# 02_MCU.net
KiCad netlist of a schematic drawn in Altium Designer
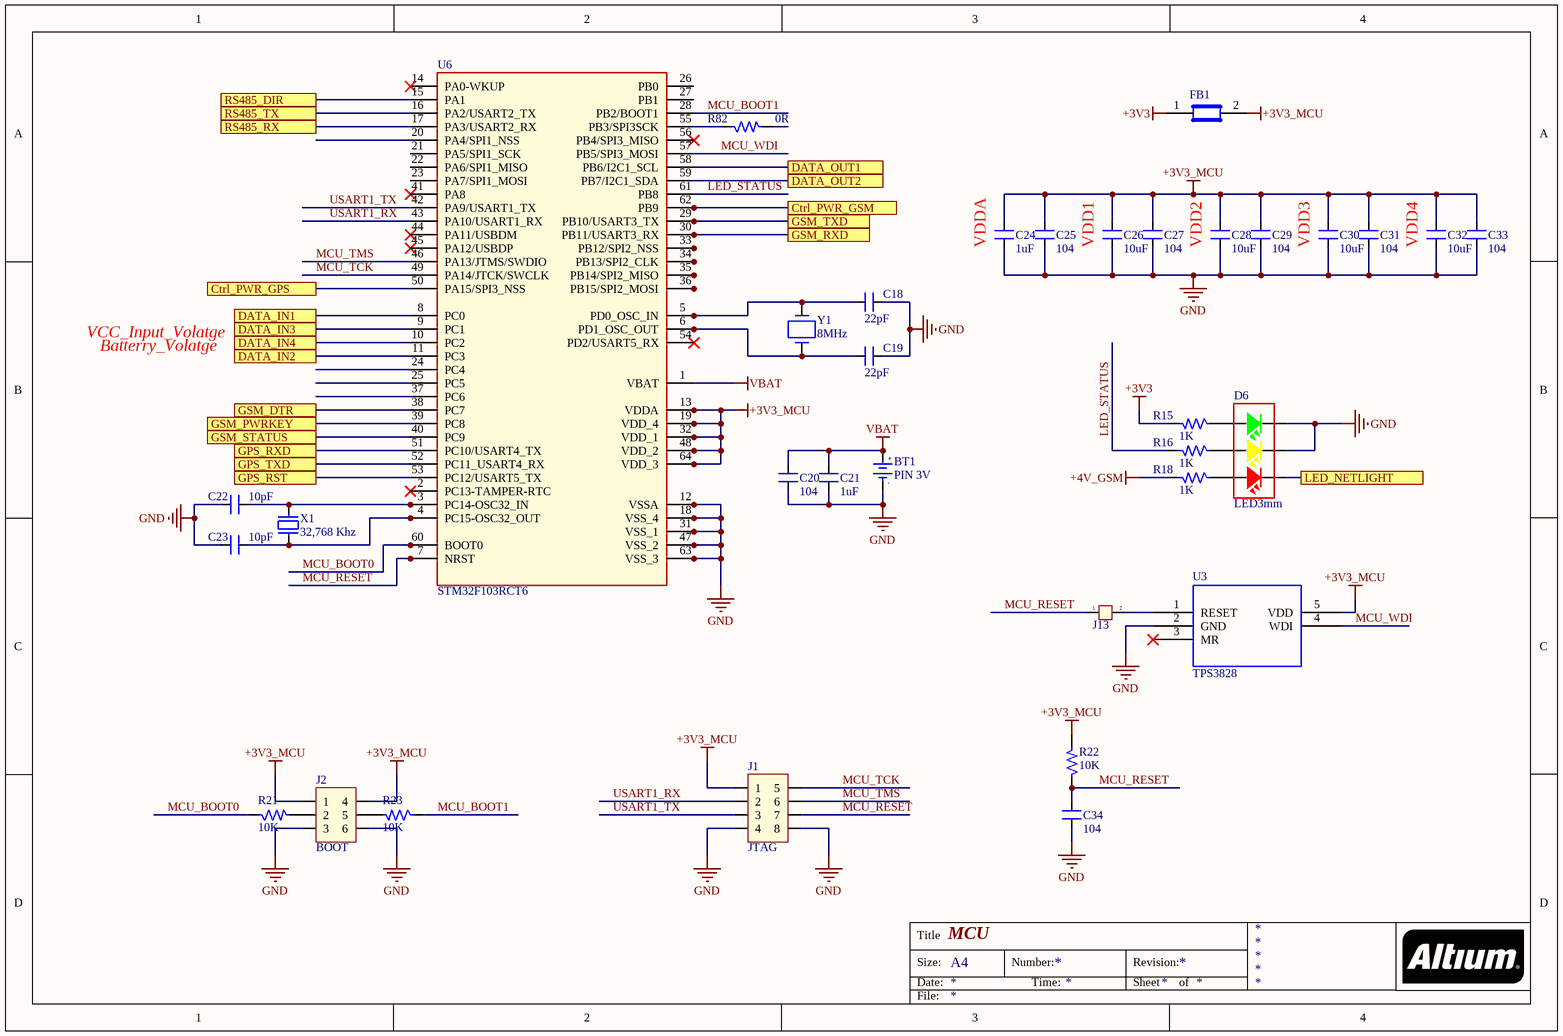
[diagram p0: [02] MCU.SchDoc]

(export (version "E")
  (design (tool "Eeschema 10.0.6"))
  (components
    (comp (ref "BT1")
      (value "PIN 3V")
      (footprint "PIN3V_mini")
      (description "Battery 3VDC")
      (libsource (lib "khapham") (part "PIN 3V"))
    )
    (comp (ref "C18")
      (value "22pF")
      (footprint "C0603 SMT")
      (description "Cap SMD")
      (libsource (lib "khapham") (part "CM"))
    )
    (comp (ref "C19")
      (value "22pF")
      (footprint "C0603 SMT")
      (description "Cap SMD")
      (libsource (lib "khapham") (part "CM"))
    )
    (comp (ref "C20")
      (value "104")
      (footprint "C0603 SMT")
      (description "Cap SMD")
      (libsource (lib "khapham") (part "CM"))
    )
    (comp (ref "C21")
      (value "1uF")
      (footprint "C0603 SMT")
      (description "Cap SMD")
      (libsource (lib "khapham") (part "CM"))
    )
    (comp (ref "C22")
      (value "10pF")
      (footprint "C0603 SMT")
      (description "Cap SMD")
      (libsource (lib "khapham") (part "CM"))
    )
    (comp (ref "C23")
      (value "10pF")
      (footprint "C0603 SMT")
      (description "Cap SMD")
      (libsource (lib "khapham") (part "CM"))
    )
    (comp (ref "C24")
      (value "1uF")
      (footprint "C0603 SMT")
      (description "Cap SMD")
      (libsource (lib "khapham") (part "CM"))
    )
    (comp (ref "C25")
      (value "104")
      (footprint "C0603 SMT")
      (description "Cap SMD")
      (libsource (lib "khapham") (part "CM"))
    )
    (comp (ref "C26")
      (value "10uF")
      (footprint "C0603 SMT")
      (description "Cap SMD")
      (libsource (lib "khapham") (part "CM"))
    )
    (comp (ref "C27")
      (value "104")
      (footprint "C0603 SMT")
      (description "Cap SMD")
      (libsource (lib "khapham") (part "CM"))
    )
    (comp (ref "C28")
      (value "10uF")
      (footprint "C0603 SMT")
      (description "Cap SMD")
      (libsource (lib "khapham") (part "CM"))
    )
    (comp (ref "C29")
      (value "104")
      (footprint "C0603 SMT")
      (description "Cap SMD")
      (libsource (lib "khapham") (part "CM"))
    )
    (comp (ref "C30")
      (value "10uF")
      (footprint "C0603 SMT")
      (description "Cap SMD")
      (libsource (lib "khapham") (part "CM"))
    )
    (comp (ref "C31")
      (value "104")
      (footprint "C0603 SMT")
      (description "Cap SMD")
      (libsource (lib "khapham") (part "CM"))
    )
    (comp (ref "C32")
      (value "10uF")
      (footprint "C0603 SMT")
      (description "Cap SMD")
      (libsource (lib "khapham") (part "CM"))
    )
    (comp (ref "C33")
      (value "104")
      (footprint "C0603 SMT")
      (description "Cap SMD")
      (libsource (lib "khapham") (part "CM"))
    )
    (comp (ref "C34")
      (value "104")
      (footprint "C0603 SMT")
      (description "Cap SMD")
      (libsource (lib "khapham") (part "CM"))
    )
    (comp (ref "D6")
      (value "LED3mm")
      (footprint "LED 3 holder 3mm")
      (description "LED 3 holder RGB 3mm")
      (libsource (lib "khapham") (part "LED3Holder_3"))
    )
    (comp (ref "FB1")
      (value "BLM21PG600SN1D")
      (footprint "R0805")
      (description "Ferrite Bead")
      (libsource (lib "khapham") (part "Ferrite Bead"))
    )
    (comp (ref "J1")
      (value "JTAG")
      (footprint "JP4x2")
      (description "Connector 4x2")
      (libsource (lib "khapham") (part "JP4x2"))
    )
    (comp (ref "J2")
      (value "BOOT")
      (footprint "JP3x2")
      (description "Connector 3x2")
      (libsource (lib "khapham") (part "JP3x2"))
    )
    (comp (ref "J13")
      (value "watdog")
      (footprint "JP2")
      (description "Jumper 2")
      (libsource (lib "khapham") (part "JP 2"))
    )
    (comp (ref "R15")
      (value "1K")
      (footprint "R0603 -SMT")
      (description "Resistor SMD")
      (libsource (lib "khapham") (part "RM"))
    )
    (comp (ref "R16")
      (value "1K")
      (footprint "R0603 -SMT")
      (description "Resistor SMD")
      (libsource (lib "khapham") (part "RM"))
    )
    (comp (ref "R18")
      (value "1K")
      (footprint "R0603 -SMT")
      (description "Resistor SMD")
      (libsource (lib "khapham") (part "RM"))
    )
    (comp (ref "R21")
      (value "10K")
      (footprint "R0603 -SMT")
      (description "Resistor SMD")
      (libsource (lib "khapham") (part "RM"))
    )
    (comp (ref "R22")
      (value "10K")
      (footprint "R0603 -SMT")
      (description "Resistor SMD")
      (libsource (lib "khapham") (part "RM"))
    )
    (comp (ref "R23")
      (value "10K")
      (footprint "R0603 -SMT")
      (description "Resistor SMD")
      (libsource (lib "khapham") (part "RM"))
    )
    (comp (ref "R82")
      (value "0R")
      (footprint "R0603 -SMT")
      (description "Resistor SMD")
      (libsource (lib "khapham") (part "RM"))
    )
    (comp (ref "U3") (value "TPS3828") (footprint "TPS3828") (libsource (lib "mlab_lib") (part "TPS3828")))
    (comp (ref "U6")
      (value "STM32F103RCT6")
      (footprint "LQFP-64")
      (description "MCU 32BIT 256KB FLASH 64LQFP")
      (libsource (lib "khapham") (part "STM32F103RCT6"))
    )
    (comp (ref "X1")
      (value "32,768 Khz")
      (footprint "XT32kn")
      (description "Crystal 32,768kHz for timer real")
      (libsource (lib "khapham") (part "XT32k"))
    )
    (comp (ref "Y1")
      (value "8MHz")
      (footprint "ABM7_v1_1_BIG")
      (description "CRYSTAL 16MHZ 18PF SMD")
      (fields
        (field (name "MANUFACTURER") "Abracon LLC")
        (field (name "MANUFACTURER PART NUMBER") "ABM7-16.000MHZ-D2Y-T")
        (field (name ".CREATOR") "MM")
        (field (name ".CHECKED PCB") "RF")
        (field (name ".CHECKED SCH") "RF")
      )
      (libsource (lib "LED_Display ") (part "ABM7-16.000MHZ-D2Y-T"))
    )
  )
  (nets
    (net (code "1") (name "+3V3") (class "Default")
      (node (ref "FB1") (pin "1") (pinfunction "1_1") (pintype "passive"))
      (node (ref "R15") (pin "2") (pinfunction "2_2") (pintype "passive"))
    )
    (net (code "2") (name "+3V3_MCU") (class "Default")
      (node (ref "C24") (pin "2") (pinfunction "2_2") (pintype "passive"))
      (node (ref "C25") (pin "2") (pinfunction "2_2") (pintype "passive"))
      (node (ref "C26") (pin "2") (pinfunction "2_2") (pintype "passive"))
      (node (ref "C27") (pin "2") (pinfunction "2_2") (pintype "passive"))
      (node (ref "C28") (pin "2") (pinfunction "2_2") (pintype "passive"))
      (node (ref "C29") (pin "2") (pinfunction "2_2") (pintype "passive"))
      (node (ref "C30") (pin "2") (pinfunction "2_2") (pintype "passive"))
      (node (ref "C31") (pin "2") (pinfunction "2_2") (pintype "passive"))
      (node (ref "C32") (pin "2") (pinfunction "2_2") (pintype "passive"))
      (node (ref "C33") (pin "2") (pinfunction "2_2") (pintype "passive"))
      (node (ref "FB1") (pin "2") (pinfunction "2_2") (pintype "passive"))
      (node (ref "J1") (pin "1") (pinfunction "1_1") (pintype "passive"))
      (node (ref "J2") (pin "1") (pinfunction "1_1") (pintype "passive"))
      (node (ref "J2") (pin "4") (pinfunction "4_4") (pintype "passive"))
      (node (ref "R22") (pin "2") (pinfunction "2_2") (pintype "passive"))
      (node (ref "U3") (pin "5") (pinfunction "VDD_5") (pintype "power_in"))
      (node (ref "U6") (pin "13") (pinfunction "VDDA_13") (pintype "passive"))
      (node (ref "U6") (pin "19") (pinfunction "VDD_4_19") (pintype "passive"))
      (node (ref "U6") (pin "32") (pinfunction "VDD_1_32") (pintype "passive"))
      (node (ref "U6") (pin "48") (pinfunction "VDD_2_48") (pintype "passive"))
      (node (ref "U6") (pin "64") (pinfunction "VDD_3_64") (pintype "passive"))
    )
    (net (code "3") (name "+4V_GSM") (class "Default")
      (node (ref "R18") (pin "2") (pinfunction "2_2") (pintype "passive"))
    )
    (net (code "4") (name "/Ctrl_PWR_GPS") (class "Default")
      (node (ref "U6") (pin "50") (pinfunction "PA15/SPI3_NSS_50") (pintype "passive"))
    )
    (net (code "5") (name "/Ctrl_PWR_GSM") (class "Default")
      (node (ref "U6") (pin "62") (pinfunction "PB9_62") (pintype "passive"))
    )
    (net (code "6") (name "/DATA_IN1") (class "Default")
      (node (ref "U6") (pin "8") (pinfunction "PC0_8") (pintype "passive"))
    )
    (net (code "7") (name "/DATA_IN2") (class "Default")
      (node (ref "U6") (pin "11") (pinfunction "PC3_11") (pintype "passive"))
    )
    (net (code "8") (name "/DATA_IN3") (class "Default")
      (node (ref "U6") (pin "9") (pinfunction "PC1_9") (pintype "passive"))
    )
    (net (code "9") (name "/DATA_IN4") (class "Default")
      (node (ref "U6") (pin "10") (pinfunction "PC2_10") (pintype "passive"))
    )
    (net (code "10") (name "/DATA_OUT1") (class "Default")
      (node (ref "U6") (pin "58") (pinfunction "PB6/I2C1_SCL_58") (pintype "passive"))
    )
    (net (code "11") (name "/DATA_OUT2") (class "Default")
      (node (ref "U6") (pin "59") (pinfunction "PB7/I2C1_SDA_59") (pintype "passive"))
    )
    (net (code "12") (name "/GPS_RST") (class "Default")
      (node (ref "U6") (pin "53") (pinfunction "PC12/USART5_TX_53") (pintype "passive"))
    )
    (net (code "13") (name "/GPS_RXD") (class "Default")
      (node (ref "U6") (pin "51") (pinfunction "PC10/USART4_TX_51") (pintype "passive"))
    )
    (net (code "14") (name "/GPS_TXD") (class "Default")
      (node (ref "U6") (pin "52") (pinfunction "PC11_USART4_RX_52") (pintype "passive"))
    )
    (net (code "15") (name "/GSM_DTR") (class "Default")
      (node (ref "U6") (pin "38") (pinfunction "PC7_38") (pintype "passive"))
    )
    (net (code "16") (name "/GSM_PWRKEY") (class "Default")
      (node (ref "U6") (pin "39") (pinfunction "PC8_39") (pintype "passive"))
    )
    (net (code "17") (name "/GSM_RXD") (class "Default")
      (node (ref "U6") (pin "30") (pinfunction "PB11/USART3_RX_30") (pintype "passive"))
    )
    (net (code "18") (name "/GSM_STATUS") (class "Default")
      (node (ref "U6") (pin "40") (pinfunction "PC9_40") (pintype "passive"))
    )
    (net (code "19") (name "/GSM_TXD") (class "Default")
      (node (ref "U6") (pin "29") (pinfunction "PB10/USART3_TX_29") (pintype "passive"))
    )
    (net (code "20") (name "/LED_NETLIGHT") (class "Default")
      (node (ref "D6") (pin "1") (pinfunction "1_1") (pintype "passive"))
    )
    (net (code "21") (name "/LED_STATUS") (class "Default")
      (node (ref "R16") (pin "2") (pinfunction "2_2") (pintype "passive"))
      (node (ref "U6") (pin "61") (pinfunction "PB8_61") (pintype "passive"))
    )
    (net (code "22") (name "/MCU_BOOT0") (class "Default")
      (node (ref "R21") (pin "1") (pinfunction "1_1") (pintype "passive"))
      (node (ref "U6") (pin "60") (pinfunction "BOOT0_60") (pintype "passive"))
    )
    (net (code "23") (name "/MCU_BOOT1") (class "Default")
      (node (ref "R23") (pin "1") (pinfunction "1_1") (pintype "passive"))
      (node (ref "U6") (pin "28") (pinfunction "PB2/BOOT1_28") (pintype "passive"))
    )
    (net (code "24") (name "/MCU_RESET") (class "Default")
      (node (ref "C34") (pin "1") (pinfunction "1_1") (pintype "passive"))
      (node (ref "J1") (pin "7") (pinfunction "7_7") (pintype "passive"))
      (node (ref "J13") (pin "1") (pinfunction "1_1") (pintype "passive"))
      (node (ref "R22") (pin "1") (pinfunction "1_1") (pintype "passive"))
      (node (ref "U6") (pin "7") (pinfunction "NRST_7") (pintype "passive"))
    )
    (net (code "25") (name "/MCU_TCK") (class "Default")
      (node (ref "J1") (pin "5") (pinfunction "5_5") (pintype "passive"))
      (node (ref "U6") (pin "49") (pinfunction "PA14/JTCK/SWCLK_49") (pintype "passive"))
    )
    (net (code "26") (name "/MCU_TMS") (class "Default")
      (node (ref "J1") (pin "6") (pinfunction "6_6") (pintype "passive"))
      (node (ref "U6") (pin "46") (pinfunction "PA13/JTMS/SWDIO_46") (pintype "passive"))
    )
    (net (code "27") (name "/MCU_WDI") (class "Default")
      (node (ref "U3") (pin "4") (pinfunction "WDI_4") (pintype "passive"))
      (node (ref "U6") (pin "57") (pinfunction "PB5/SPI3_MOSI_57") (pintype "passive"))
    )
    (net (code "28") (name "/RS485_DIR") (class "Default")
      (node (ref "U6") (pin "15") (pinfunction "PA1_15") (pintype "passive"))
    )
    (net (code "29") (name "/RS485_RX") (class "Default")
      (node (ref "U6") (pin "17") (pinfunction "PA3/USART2_RX_17") (pintype "passive"))
    )
    (net (code "30") (name "/RS485_TX") (class "Default")
      (node (ref "U6") (pin "16") (pinfunction "PA2/USART2_TX_16") (pintype "passive"))
    )
    (net (code "31") (name "/USART1_RX") (class "Default")
      (node (ref "J1") (pin "2") (pinfunction "2_2") (pintype "passive"))
      (node (ref "U6") (pin "43") (pinfunction "PA10/USART1_RX_43") (pintype "passive"))
    )
    (net (code "32") (name "/USART1_TX") (class "Default")
      (node (ref "J1") (pin "3") (pinfunction "3_3") (pintype "passive"))
      (node (ref "U6") (pin "42") (pinfunction "PA9/USART1_TX_42") (pintype "passive"))
    )
    (net (code "33") (name "GND") (class "Default")
      (node (ref "BT1") (pin "2") (pinfunction "GND_2") (pintype "passive"))
      (node (ref "C18") (pin "2") (pinfunction "2_2") (pintype "passive"))
      (node (ref "C19") (pin "2") (pinfunction "2_2") (pintype "passive"))
      (node (ref "C20") (pin "1") (pinfunction "1_1") (pintype "passive"))
      (node (ref "C21") (pin "1") (pinfunction "1_1") (pintype "passive"))
      (node (ref "C22") (pin "2") (pinfunction "2_2") (pintype "passive"))
      (node (ref "C23") (pin "2") (pinfunction "2_2") (pintype "passive"))
      (node (ref "C24") (pin "1") (pinfunction "1_1") (pintype "passive"))
      (node (ref "C25") (pin "1") (pinfunction "1_1") (pintype "passive"))
      (node (ref "C26") (pin "1") (pinfunction "1_1") (pintype "passive"))
      (node (ref "C27") (pin "1") (pinfunction "1_1") (pintype "passive"))
      (node (ref "C28") (pin "1") (pinfunction "1_1") (pintype "passive"))
      (node (ref "C29") (pin "1") (pinfunction "1_1") (pintype "passive"))
      (node (ref "C30") (pin "1") (pinfunction "1_1") (pintype "passive"))
      (node (ref "C31") (pin "1") (pinfunction "1_1") (pintype "passive"))
      (node (ref "C32") (pin "1") (pinfunction "1_1") (pintype "passive"))
      (node (ref "C33") (pin "1") (pinfunction "1_1") (pintype "passive"))
      (node (ref "C34") (pin "2") (pinfunction "2_2") (pintype "passive"))
      (node (ref "D6") (pin "3") (pinfunction "3_3") (pintype "passive"))
      (node (ref "D6") (pin "5") (pinfunction "5_5") (pintype "passive"))
      (node (ref "J1") (pin "4") (pinfunction "4_4") (pintype "passive"))
      (node (ref "J1") (pin "8") (pinfunction "8_8") (pintype "passive"))
      (node (ref "J2") (pin "3") (pinfunction "3_3") (pintype "passive"))
      (node (ref "J2") (pin "6") (pinfunction "6_6") (pintype "passive"))
      (node (ref "U3") (pin "2") (pinfunction "GND_2") (pintype "power_in"))
      (node (ref "U6") (pin "12") (pinfunction "VSSA_12") (pintype "passive"))
      (node (ref "U6") (pin "18") (pinfunction "VSS_4_18") (pintype "passive"))
      (node (ref "U6") (pin "31") (pinfunction "VSS_1_31") (pintype "passive"))
      (node (ref "U6") (pin "47") (pinfunction "VSS_2_47") (pintype "passive"))
      (node (ref "U6") (pin "63") (pinfunction "VSS_3_63") (pintype "passive"))
    )
    (net (code "34") (name "Net-(D6-Pad2)") (class "Default")
      (node (ref "D6") (pin "2") (pinfunction "2_2") (pintype "passive"))
      (node (ref "R18") (pin "1") (pinfunction "1_1") (pintype "passive"))
    )
    (net (code "35") (name "Net-(D6-Pad4)") (class "Default")
      (node (ref "D6") (pin "4") (pinfunction "4_4") (pintype "passive"))
      (node (ref "R16") (pin "1") (pinfunction "1_1") (pintype "passive"))
    )
    (net (code "36") (name "Net-(D6-Pad6)") (class "Default")
      (node (ref "D6") (pin "6") (pinfunction "6_6") (pintype "passive"))
      (node (ref "R15") (pin "1") (pinfunction "1_1") (pintype "passive"))
    )
    (net (code "37") (name "Net-(J2-Pad2)") (class "Default")
      (node (ref "J2") (pin "2") (pinfunction "2_2") (pintype "passive"))
      (node (ref "R21") (pin "2") (pinfunction "2_2") (pintype "passive"))
    )
    (net (code "38") (name "Net-(J2-Pad5)") (class "Default")
      (node (ref "J2") (pin "5") (pinfunction "5_5") (pintype "passive"))
      (node (ref "R23") (pin "2") (pinfunction "2_2") (pintype "passive"))
    )
    (net (code "39") (name "Net-(U3-RESET)") (class "Default")
      (node (ref "J13") (pin "2") (pinfunction "2_2") (pintype "passive"))
      (node (ref "U3") (pin "1") (pinfunction "RESET_1") (pintype "passive"))
    )
    (net (code "40") (name "Net-(U6-PB3{slash}SPI3SCK)") (class "Default")
      (node (ref "R82") (pin "1") (pinfunction "1_1") (pintype "passive"))
      (node (ref "U6") (pin "55") (pinfunction "PB3/SPI3SCK_55") (pintype "passive"))
    )
    (net (code "41") (name "Net-(U6-PC14-OSC32_IN)") (class "Default")
      (node (ref "C22") (pin "1") (pinfunction "1_1") (pintype "passive"))
      (node (ref "U6") (pin "3") (pinfunction "PC14-OSC32_IN_3") (pintype "passive"))
      (node (ref "X1") (pin "1") (pinfunction "1_1") (pintype "passive"))
    )
    (net (code "42") (name "Net-(U6-PC15-OSC32_OUT)") (class "Default")
      (node (ref "C23") (pin "1") (pinfunction "1_1") (pintype "passive"))
      (node (ref "U6") (pin "4") (pinfunction "PC15-OSC32_OUT_4") (pintype "passive"))
      (node (ref "X1") (pin "2") (pinfunction "2_2") (pintype "passive"))
    )
    (net (code "43") (name "Net-(U6-PD0_OSC_IN)") (class "Default")
      (node (ref "C18") (pin "1") (pinfunction "1_1") (pintype "passive"))
      (node (ref "U6") (pin "5") (pinfunction "PD0_OSC_IN_5") (pintype "passive"))
      (node (ref "Y1") (pin "2") (pinfunction "2_2") (pintype "passive"))
    )
    (net (code "44") (name "Net-(U6-PD1_OSC_OUT)") (class "Default")
      (node (ref "C19") (pin "1") (pinfunction "1_1") (pintype "passive"))
      (node (ref "U6") (pin "6") (pinfunction "PD1_OSC_OUT_6") (pintype "passive"))
      (node (ref "Y1") (pin "1") (pinfunction "1_1") (pintype "passive"))
    )
    (net (code "45") (name "VBAT") (class "Default")
      (node (ref "BT1") (pin "1") (pinfunction "+3V_1") (pintype "passive"))
      (node (ref "C20") (pin "2") (pinfunction "2_2") (pintype "passive"))
      (node (ref "C21") (pin "2") (pinfunction "2_2") (pintype "passive"))
      (node (ref "U6") (pin "1") (pinfunction "VBAT_1") (pintype "passive"))
    )
    (net (code "46") (name "unconnected-(R82-Pad2)") (class "Default")
      (node (ref "R82") (pin "2") (pinfunction "2_2") (pintype "passive"))
    )
    (net (code "47") (name "unconnected-(U3-MR-Pad3)") (class "Default")
      (node (ref "U3") (pin "3") (pinfunction "MR_3") (pintype "passive+no_connect"))
    )
    (net (code "48") (name "unconnected-(U6-PA0-WKUP-Pad14)") (class "Default")
      (node (ref "U6") (pin "14") (pinfunction "PA0-WKUP_14") (pintype "passive+no_connect"))
    )
    (net (code "49") (name "unconnected-(U6-PA4{slash}SPI1_NSS-Pad20)") (class "Default")
      (node (ref "U6") (pin "20") (pinfunction "PA4/SPI1_NSS_20") (pintype "passive"))
    )
    (net (code "50") (name "unconnected-(U6-PA5{slash}SPI1_SCK-Pad21)") (class "Default")
      (node (ref "U6") (pin "21") (pinfunction "PA5/SPI1_SCK_21") (pintype "passive"))
    )
    (net (code "51") (name "unconnected-(U6-PA6{slash}SPI1_MISO-Pad22)") (class "Default")
      (node (ref "U6") (pin "22") (pinfunction "PA6/SPI1_MISO_22") (pintype "passive"))
    )
    (net (code "52") (name "unconnected-(U6-PA7{slash}SPI1_MOSI-Pad23)") (class "Default")
      (node (ref "U6") (pin "23") (pinfunction "PA7/SPI1_MOSI_23") (pintype "passive"))
    )
    (net (code "53") (name "unconnected-(U6-PA8-Pad41)") (class "Default")
      (node (ref "U6") (pin "41") (pinfunction "PA8_41") (pintype "passive+no_connect"))
    )
    (net (code "54") (name "unconnected-(U6-PA11{slash}USBDM-Pad44)") (class "Default")
      (node (ref "U6") (pin "44") (pinfunction "PA11/USBDM_44") (pintype "passive+no_connect"))
    )
    (net (code "55") (name "unconnected-(U6-PA12{slash}USBDP-Pad45)") (class "Default")
      (node (ref "U6") (pin "45") (pinfunction "PA12/USBDP_45") (pintype "passive+no_connect"))
    )
    (net (code "56") (name "unconnected-(U6-PB0-Pad26)") (class "Default")
      (node (ref "U6") (pin "26") (pinfunction "PB0_26") (pintype "passive"))
    )
    (net (code "57") (name "unconnected-(U6-PB1-Pad27)") (class "Default")
      (node (ref "U6") (pin "27") (pinfunction "PB1_27") (pintype "passive"))
    )
    (net (code "58") (name "unconnected-(U6-PB4{slash}SPI3_MISO-Pad56)") (class "Default")
      (node (ref "U6") (pin "56") (pinfunction "PB4/SPI3_MISO_56") (pintype "passive+no_connect"))
    )
    (net (code "59") (name "unconnected-(U6-PB12{slash}SPI2_NSS-Pad33)") (class "Default")
      (node (ref "U6") (pin "33") (pinfunction "PB12/SPI2_NSS_33") (pintype "passive"))
    )
    (net (code "60") (name "unconnected-(U6-PB13{slash}SPI2_CLK-Pad34)") (class "Default")
      (node (ref "U6") (pin "34") (pinfunction "PB13/SPI2_CLK_34") (pintype "passive"))
    )
    (net (code "61") (name "unconnected-(U6-PB14{slash}SPI2_MISO-Pad35)") (class "Default")
      (node (ref "U6") (pin "35") (pinfunction "PB14/SPI2_MISO_35") (pintype "passive"))
    )
    (net (code "62") (name "unconnected-(U6-PB15{slash}SPI2_MOSI-Pad36)") (class "Default")
      (node (ref "U6") (pin "36") (pinfunction "PB15/SPI2_MOSI_36") (pintype "passive"))
    )
    (net (code "63") (name "unconnected-(U6-PC4-Pad24)") (class "Default")
      (node (ref "U6") (pin "24") (pinfunction "PC4_24") (pintype "passive"))
    )
    (net (code "64") (name "unconnected-(U6-PC5-Pad25)") (class "Default")
      (node (ref "U6") (pin "25") (pinfunction "PC5_25") (pintype "passive"))
    )
    (net (code "65") (name "unconnected-(U6-PC6-Pad37)") (class "Default")
      (node (ref "U6") (pin "37") (pinfunction "PC6_37") (pintype "passive"))
    )
    (net (code "66") (name "unconnected-(U6-PC13-TAMPER-RTC-Pad2)") (class "Default")
      (node (ref "U6") (pin "2") (pinfunction "PC13-TAMPER-RTC_2") (pintype "passive+no_connect"))
    )
    (net (code "67") (name "unconnected-(U6-PD2{slash}USART5_RX-Pad54)") (class "Default")
      (node (ref "U6") (pin "54") (pinfunction "PD2/USART5_RX_54") (pintype "passive+no_connect"))
    )
  )
)
